# eCog001_Proto_PTH.net
KiCad netlist of a schematic drawn in EAGLE
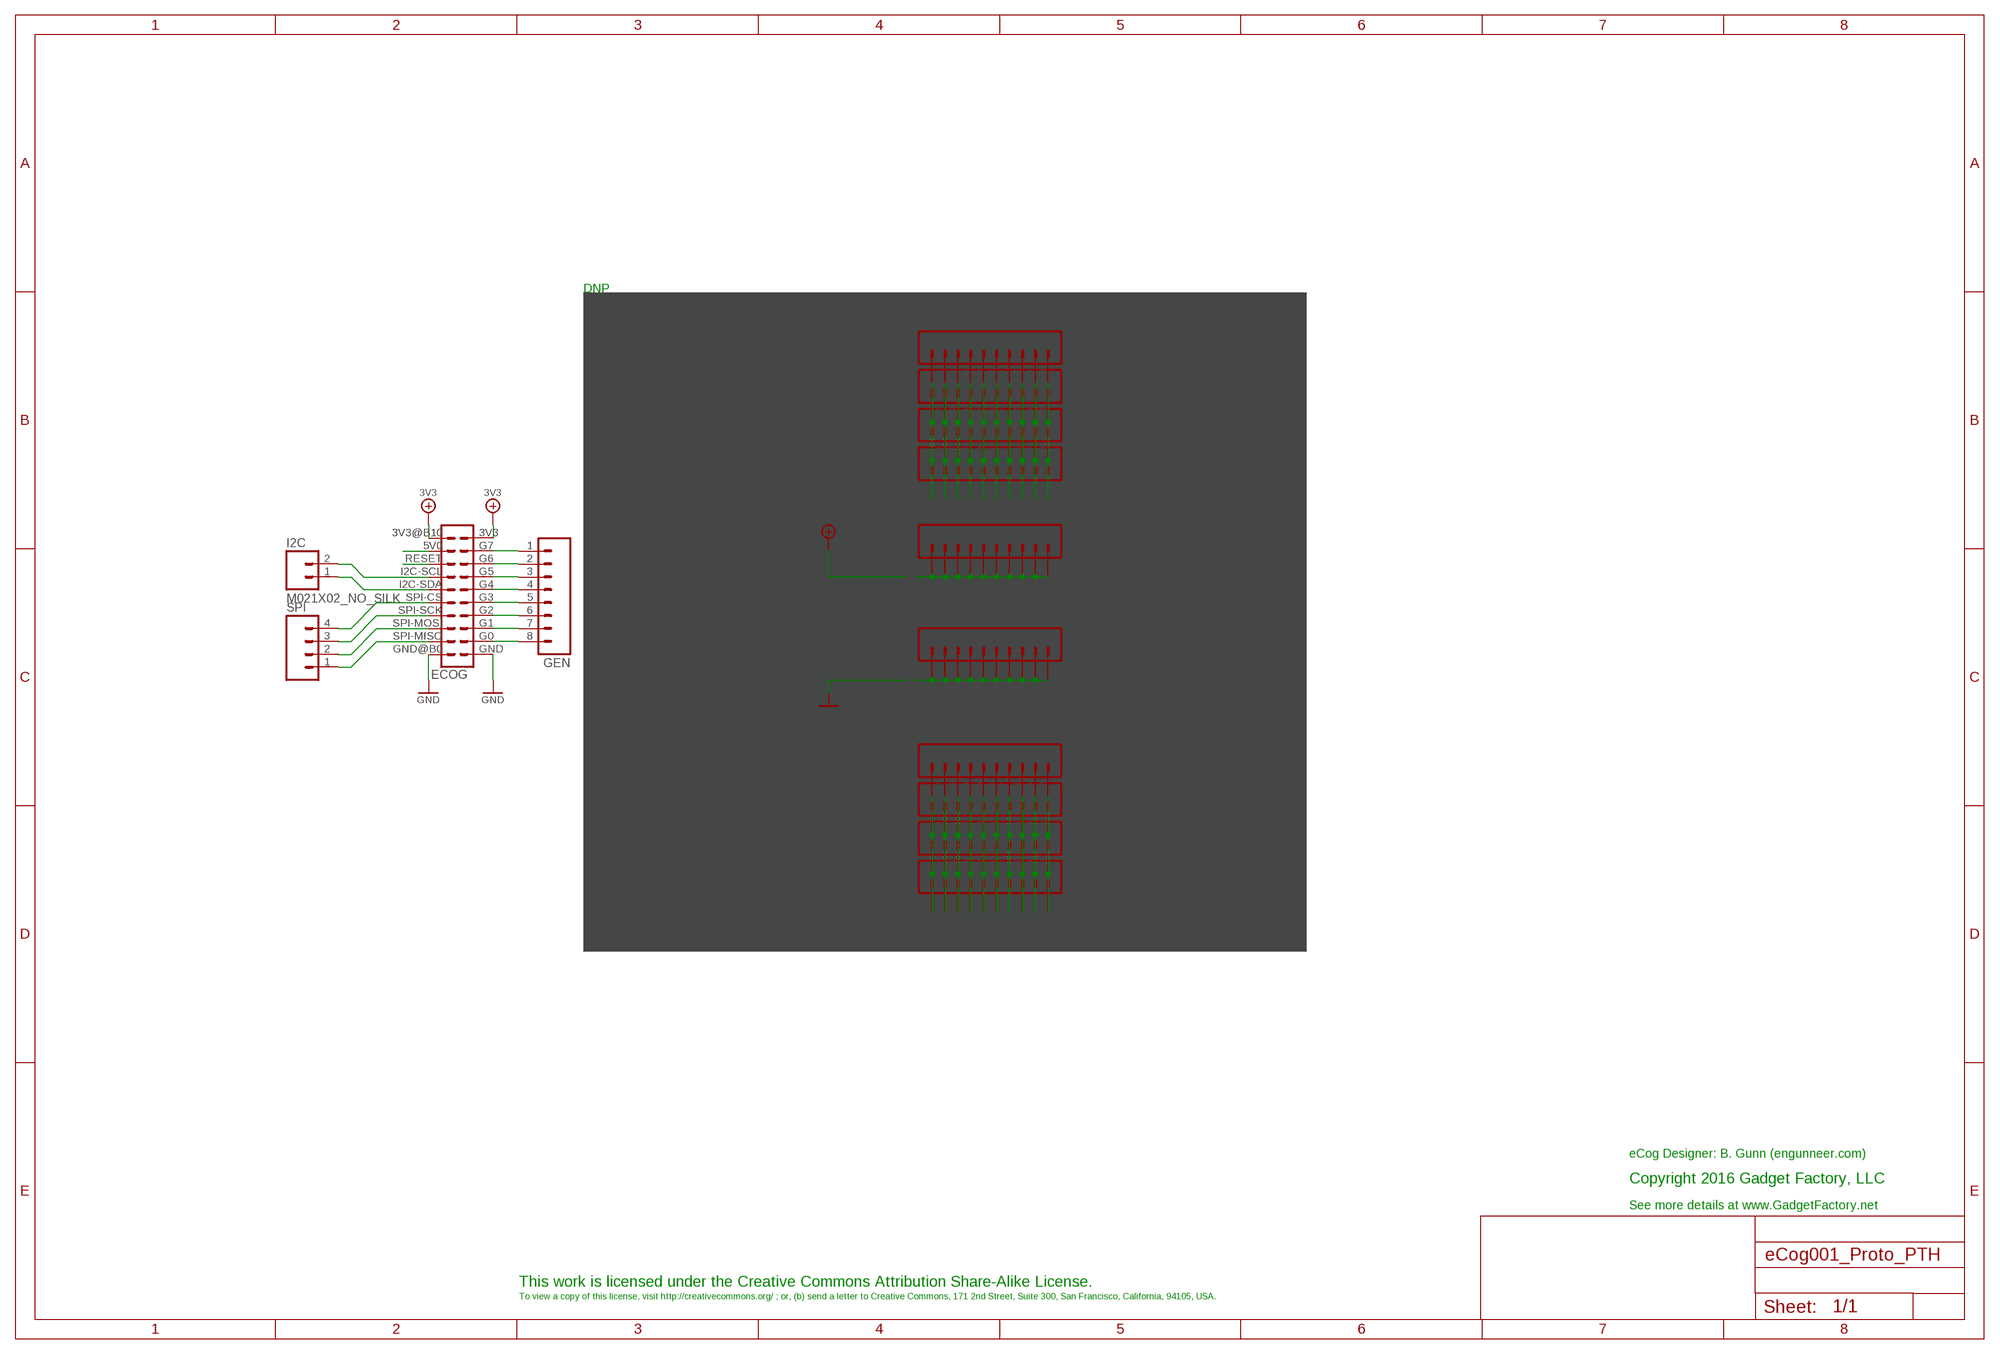
[diagram p0: schematic, sheet 1]

(export (version "E")
  (design (tool "Eeschema 10.0.6"))
  (components
    (comp (ref "ECOG")
      (value "ECOG_DUALTHROUGHHOLE")
      (footprint "eagle-import:ECOG_DUAL_TH")
      (libsource (lib "eagle-import") (part "ECOG_DUALTHROUGHHOLE"))
    )
    (comp (ref "GEN")
      (value "M08NO_SILK")
      (footprint "eagle-import:1X08_NO_SILK")
      (libsource (lib "eagle-import") (part "M08NO_SILK"))
    )
    (comp (ref "GND")
      (value "M10NO_SILK")
      (footprint "eagle-import:1X10_NO_SILK")
      (libsource (lib "eagle-import") (part "M10NO_SILK"))
    )
    (comp (ref "I2C")
      (value "M021X02_NO_SILK")
      (footprint "eagle-import:1X02_NO_SILK")
      (libsource (lib "eagle-import") (part "M021X02_NO_SILK"))
    )
    (comp (ref "P1")
      (value "M10NO_SILK")
      (footprint "eagle-import:1X10_NO_SILK")
      (libsource (lib "eagle-import") (part "M10NO_SILK"))
    )
    (comp (ref "P2")
      (value "M10NO_SILK")
      (footprint "eagle-import:1X10_NO_SILK")
      (libsource (lib "eagle-import") (part "M10NO_SILK"))
    )
    (comp (ref "P3")
      (value "M10NO_SILK")
      (footprint "eagle-import:1X10_NO_SILK")
      (libsource (lib "eagle-import") (part "M10NO_SILK"))
    )
    (comp (ref "P4")
      (value "M10NO_SILK")
      (footprint "eagle-import:1X10_NO_SILK")
      (libsource (lib "eagle-import") (part "M10NO_SILK"))
    )
    (comp (ref "P5")
      (value "M10NO_SILK")
      (footprint "eagle-import:1X10_NO_SILK")
      (libsource (lib "eagle-import") (part "M10NO_SILK"))
    )
    (comp (ref "P6")
      (value "M10NO_SILK")
      (footprint "eagle-import:1X10_NO_SILK")
      (libsource (lib "eagle-import") (part "M10NO_SILK"))
    )
    (comp (ref "P7")
      (value "M10NO_SILK")
      (footprint "eagle-import:1X10_NO_SILK")
      (libsource (lib "eagle-import") (part "M10NO_SILK"))
    )
    (comp (ref "P8")
      (value "M10NO_SILK")
      (footprint "eagle-import:1X10_NO_SILK")
      (libsource (lib "eagle-import") (part "M10NO_SILK"))
    )
    (comp (ref "SPI")
      (value "M041X04_NO_SILK")
      (footprint "eagle-import:1X04_NO_SILK")
      (libsource (lib "eagle-import") (part "M041X04_NO_SILK"))
    )
    (comp (ref "VCC")
      (value "M10NO_SILK")
      (footprint "eagle-import:1X10_NO_SILK")
      (libsource (lib "eagle-import") (part "M10NO_SILK"))
    )
  )
  (nets
    (net (code "1") (name "3V3") (class "Default")
      (node (ref "ECOG") (pin "3V3") (pinfunction "3V3_3V3") (pintype "passive"))
      (node (ref "ECOG") (pin "3V3@B10") (pinfunction "3V3_3V3@B10") (pintype "passive"))
      (node (ref "VCC") (pin "1") (pinfunction "1_1") (pintype "passive"))
      (node (ref "VCC") (pin "10") (pinfunction "10_10") (pintype "passive"))
      (node (ref "VCC") (pin "2") (pinfunction "2_2") (pintype "passive"))
      (node (ref "VCC") (pin "3") (pinfunction "3_3") (pintype "passive"))
      (node (ref "VCC") (pin "4") (pinfunction "4_4") (pintype "passive"))
      (node (ref "VCC") (pin "5") (pinfunction "5_5") (pintype "passive"))
      (node (ref "VCC") (pin "6") (pinfunction "6_6") (pintype "passive"))
      (node (ref "VCC") (pin "7") (pinfunction "7_7") (pintype "passive"))
      (node (ref "VCC") (pin "8") (pinfunction "8_8") (pintype "passive"))
      (node (ref "VCC") (pin "9") (pinfunction "9_9") (pintype "passive"))
    )
    (net (code "2") (name "GND") (class "Default")
      (node (ref "ECOG") (pin "GND") (pinfunction "GND_GND") (pintype "passive"))
      (node (ref "ECOG") (pin "GND@B0") (pinfunction "GND_GND@B0") (pintype "passive"))
      (node (ref "GND") (pin "1") (pinfunction "1_1") (pintype "passive"))
      (node (ref "GND") (pin "10") (pinfunction "10_10") (pintype "passive"))
      (node (ref "GND") (pin "2") (pinfunction "2_2") (pintype "passive"))
      (node (ref "GND") (pin "3") (pinfunction "3_3") (pintype "passive"))
      (node (ref "GND") (pin "4") (pinfunction "4_4") (pintype "passive"))
      (node (ref "GND") (pin "5") (pinfunction "5_5") (pintype "passive"))
      (node (ref "GND") (pin "6") (pinfunction "6_6") (pintype "passive"))
      (node (ref "GND") (pin "7") (pinfunction "7_7") (pintype "passive"))
      (node (ref "GND") (pin "8") (pinfunction "8_8") (pintype "passive"))
      (node (ref "GND") (pin "9") (pinfunction "9_9") (pintype "passive"))
    )
    (net (code "3") (name "Net-(ECOG-PadG0)") (class "Default")
      (node (ref "ECOG") (pin "G0") (pinfunction "G0_G0") (pintype "passive"))
      (node (ref "GEN") (pin "8") (pinfunction "8_8") (pintype "passive"))
    )
    (net (code "4") (name "Net-(ECOG-PadG1)") (class "Default")
      (node (ref "ECOG") (pin "G1") (pinfunction "G1_G1") (pintype "passive"))
      (node (ref "GEN") (pin "7") (pinfunction "7_7") (pintype "passive"))
    )
    (net (code "5") (name "Net-(ECOG-PadG2)") (class "Default")
      (node (ref "ECOG") (pin "G2") (pinfunction "G2_G2") (pintype "passive"))
      (node (ref "GEN") (pin "6") (pinfunction "6_6") (pintype "passive"))
    )
    (net (code "6") (name "Net-(ECOG-PadG3)") (class "Default")
      (node (ref "ECOG") (pin "G3") (pinfunction "G3_G3") (pintype "passive"))
      (node (ref "GEN") (pin "5") (pinfunction "5_5") (pintype "passive"))
    )
    (net (code "7") (name "Net-(ECOG-PadG4)") (class "Default")
      (node (ref "ECOG") (pin "G4") (pinfunction "G4_G4") (pintype "passive"))
      (node (ref "GEN") (pin "4") (pinfunction "4_4") (pintype "passive"))
    )
    (net (code "8") (name "Net-(ECOG-PadG5)") (class "Default")
      (node (ref "ECOG") (pin "G5") (pinfunction "G5_G5") (pintype "passive"))
      (node (ref "GEN") (pin "3") (pinfunction "3_3") (pintype "passive"))
    )
    (net (code "9") (name "Net-(ECOG-PadG6)") (class "Default")
      (node (ref "ECOG") (pin "G6") (pinfunction "G6_G6") (pintype "passive"))
      (node (ref "GEN") (pin "2") (pinfunction "2_2") (pintype "passive"))
    )
    (net (code "10") (name "Net-(ECOG-PadG7)") (class "Default")
      (node (ref "ECOG") (pin "G7") (pinfunction "G7_G7") (pintype "passive"))
      (node (ref "GEN") (pin "1") (pinfunction "1_1") (pintype "passive"))
    )
    (net (code "11") (name "Net-(ECOG-PadI2C-SCL)") (class "Default")
      (node (ref "ECOG") (pin "I2C-SCL") (pinfunction "I2C-SCL_I2C-SCL") (pintype "passive"))
      (node (ref "I2C") (pin "2") (pinfunction "2_2") (pintype "passive"))
    )
    (net (code "12") (name "Net-(ECOG-PadI2C-SDA)") (class "Default")
      (node (ref "ECOG") (pin "I2C-SDA") (pinfunction "I2C-SDA_I2C-SDA") (pintype "passive"))
      (node (ref "I2C") (pin "1") (pinfunction "1_1") (pintype "passive"))
    )
    (net (code "13") (name "Net-(ECOG-PadSPI-CS)") (class "Default")
      (node (ref "ECOG") (pin "SPI-CS") (pinfunction "SPI-CS_SPI-CS") (pintype "passive"))
      (node (ref "SPI") (pin "4") (pinfunction "4_4") (pintype "passive"))
    )
    (net (code "14") (name "Net-(ECOG-PadSPI-MISO)") (class "Default")
      (node (ref "ECOG") (pin "SPI-MISO") (pinfunction "SPI-MISO_SPI-MISO") (pintype "passive"))
      (node (ref "SPI") (pin "1") (pinfunction "1_1") (pintype "passive"))
    )
    (net (code "15") (name "Net-(ECOG-PadSPI-MOSI)") (class "Default")
      (node (ref "ECOG") (pin "SPI-MOSI") (pinfunction "SPI-MOSI_SPI-MOSI") (pintype "passive"))
      (node (ref "SPI") (pin "2") (pinfunction "2_2") (pintype "passive"))
    )
    (net (code "16") (name "Net-(ECOG-PadSPI-SCK)") (class "Default")
      (node (ref "ECOG") (pin "SPI-SCK") (pinfunction "SPI-SCK_SPI-SCK") (pintype "passive"))
      (node (ref "SPI") (pin "3") (pinfunction "3_3") (pintype "passive"))
    )
    (net (code "17") (name "Net-(P1-Pad1)") (class "Default")
      (node (ref "P1") (pin "1") (pinfunction "1_1") (pintype "passive"))
      (node (ref "P2") (pin "1") (pinfunction "1_1") (pintype "passive"))
      (node (ref "P3") (pin "1") (pinfunction "1_1") (pintype "passive"))
      (node (ref "P4") (pin "1") (pinfunction "1_1") (pintype "passive"))
    )
    (net (code "18") (name "Net-(P1-Pad2)") (class "Default")
      (node (ref "P1") (pin "2") (pinfunction "2_2") (pintype "passive"))
      (node (ref "P2") (pin "2") (pinfunction "2_2") (pintype "passive"))
      (node (ref "P3") (pin "2") (pinfunction "2_2") (pintype "passive"))
      (node (ref "P4") (pin "2") (pinfunction "2_2") (pintype "passive"))
    )
    (net (code "19") (name "Net-(P1-Pad3)") (class "Default")
      (node (ref "P1") (pin "3") (pinfunction "3_3") (pintype "passive"))
      (node (ref "P2") (pin "3") (pinfunction "3_3") (pintype "passive"))
      (node (ref "P3") (pin "3") (pinfunction "3_3") (pintype "passive"))
      (node (ref "P4") (pin "3") (pinfunction "3_3") (pintype "passive"))
    )
    (net (code "20") (name "Net-(P1-Pad4)") (class "Default")
      (node (ref "P1") (pin "4") (pinfunction "4_4") (pintype "passive"))
      (node (ref "P2") (pin "4") (pinfunction "4_4") (pintype "passive"))
      (node (ref "P3") (pin "4") (pinfunction "4_4") (pintype "passive"))
      (node (ref "P4") (pin "4") (pinfunction "4_4") (pintype "passive"))
    )
    (net (code "21") (name "Net-(P1-Pad5)") (class "Default")
      (node (ref "P1") (pin "5") (pinfunction "5_5") (pintype "passive"))
      (node (ref "P2") (pin "5") (pinfunction "5_5") (pintype "passive"))
      (node (ref "P3") (pin "5") (pinfunction "5_5") (pintype "passive"))
      (node (ref "P4") (pin "5") (pinfunction "5_5") (pintype "passive"))
    )
    (net (code "22") (name "Net-(P1-Pad6)") (class "Default")
      (node (ref "P1") (pin "6") (pinfunction "6_6") (pintype "passive"))
      (node (ref "P2") (pin "6") (pinfunction "6_6") (pintype "passive"))
      (node (ref "P3") (pin "6") (pinfunction "6_6") (pintype "passive"))
      (node (ref "P4") (pin "6") (pinfunction "6_6") (pintype "passive"))
    )
    (net (code "23") (name "Net-(P1-Pad7)") (class "Default")
      (node (ref "P1") (pin "7") (pinfunction "7_7") (pintype "passive"))
      (node (ref "P2") (pin "7") (pinfunction "7_7") (pintype "passive"))
      (node (ref "P3") (pin "7") (pinfunction "7_7") (pintype "passive"))
      (node (ref "P4") (pin "7") (pinfunction "7_7") (pintype "passive"))
    )
    (net (code "24") (name "Net-(P1-Pad8)") (class "Default")
      (node (ref "P1") (pin "8") (pinfunction "8_8") (pintype "passive"))
      (node (ref "P2") (pin "8") (pinfunction "8_8") (pintype "passive"))
      (node (ref "P3") (pin "8") (pinfunction "8_8") (pintype "passive"))
      (node (ref "P4") (pin "8") (pinfunction "8_8") (pintype "passive"))
    )
    (net (code "25") (name "Net-(P1-Pad9)") (class "Default")
      (node (ref "P1") (pin "9") (pinfunction "9_9") (pintype "passive"))
      (node (ref "P2") (pin "9") (pinfunction "9_9") (pintype "passive"))
      (node (ref "P3") (pin "9") (pinfunction "9_9") (pintype "passive"))
      (node (ref "P4") (pin "9") (pinfunction "9_9") (pintype "passive"))
    )
    (net (code "26") (name "Net-(P1-Pad10)") (class "Default")
      (node (ref "P1") (pin "10") (pinfunction "10_10") (pintype "passive"))
      (node (ref "P2") (pin "10") (pinfunction "10_10") (pintype "passive"))
      (node (ref "P3") (pin "10") (pinfunction "10_10") (pintype "passive"))
      (node (ref "P4") (pin "10") (pinfunction "10_10") (pintype "passive"))
    )
    (net (code "27") (name "Net-(P5-Pad1)") (class "Default")
      (node (ref "P5") (pin "1") (pinfunction "1_1") (pintype "passive"))
      (node (ref "P6") (pin "1") (pinfunction "1_1") (pintype "passive"))
      (node (ref "P7") (pin "1") (pinfunction "1_1") (pintype "passive"))
      (node (ref "P8") (pin "1") (pinfunction "1_1") (pintype "passive"))
    )
    (net (code "28") (name "Net-(P5-Pad2)") (class "Default")
      (node (ref "P5") (pin "2") (pinfunction "2_2") (pintype "passive"))
      (node (ref "P6") (pin "2") (pinfunction "2_2") (pintype "passive"))
      (node (ref "P7") (pin "2") (pinfunction "2_2") (pintype "passive"))
      (node (ref "P8") (pin "2") (pinfunction "2_2") (pintype "passive"))
    )
    (net (code "29") (name "Net-(P5-Pad3)") (class "Default")
      (node (ref "P5") (pin "3") (pinfunction "3_3") (pintype "passive"))
      (node (ref "P6") (pin "3") (pinfunction "3_3") (pintype "passive"))
      (node (ref "P7") (pin "3") (pinfunction "3_3") (pintype "passive"))
      (node (ref "P8") (pin "3") (pinfunction "3_3") (pintype "passive"))
    )
    (net (code "30") (name "Net-(P5-Pad4)") (class "Default")
      (node (ref "P5") (pin "4") (pinfunction "4_4") (pintype "passive"))
      (node (ref "P6") (pin "4") (pinfunction "4_4") (pintype "passive"))
      (node (ref "P7") (pin "4") (pinfunction "4_4") (pintype "passive"))
      (node (ref "P8") (pin "4") (pinfunction "4_4") (pintype "passive"))
    )
    (net (code "31") (name "Net-(P5-Pad5)") (class "Default")
      (node (ref "P5") (pin "5") (pinfunction "5_5") (pintype "passive"))
      (node (ref "P6") (pin "5") (pinfunction "5_5") (pintype "passive"))
      (node (ref "P7") (pin "5") (pinfunction "5_5") (pintype "passive"))
      (node (ref "P8") (pin "5") (pinfunction "5_5") (pintype "passive"))
    )
    (net (code "32") (name "Net-(P5-Pad6)") (class "Default")
      (node (ref "P5") (pin "6") (pinfunction "6_6") (pintype "passive"))
      (node (ref "P6") (pin "6") (pinfunction "6_6") (pintype "passive"))
      (node (ref "P7") (pin "6") (pinfunction "6_6") (pintype "passive"))
      (node (ref "P8") (pin "6") (pinfunction "6_6") (pintype "passive"))
    )
    (net (code "33") (name "Net-(P5-Pad7)") (class "Default")
      (node (ref "P5") (pin "7") (pinfunction "7_7") (pintype "passive"))
      (node (ref "P6") (pin "7") (pinfunction "7_7") (pintype "passive"))
      (node (ref "P7") (pin "7") (pinfunction "7_7") (pintype "passive"))
      (node (ref "P8") (pin "7") (pinfunction "7_7") (pintype "passive"))
    )
    (net (code "34") (name "Net-(P5-Pad8)") (class "Default")
      (node (ref "P5") (pin "8") (pinfunction "8_8") (pintype "passive"))
      (node (ref "P6") (pin "8") (pinfunction "8_8") (pintype "passive"))
      (node (ref "P7") (pin "8") (pinfunction "8_8") (pintype "passive"))
      (node (ref "P8") (pin "8") (pinfunction "8_8") (pintype "passive"))
    )
    (net (code "35") (name "Net-(P5-Pad9)") (class "Default")
      (node (ref "P5") (pin "9") (pinfunction "9_9") (pintype "passive"))
      (node (ref "P6") (pin "9") (pinfunction "9_9") (pintype "passive"))
      (node (ref "P7") (pin "9") (pinfunction "9_9") (pintype "passive"))
      (node (ref "P8") (pin "9") (pinfunction "9_9") (pintype "passive"))
    )
    (net (code "36") (name "Net-(P5-Pad10)") (class "Default")
      (node (ref "P5") (pin "10") (pinfunction "10_10") (pintype "passive"))
      (node (ref "P6") (pin "10") (pinfunction "10_10") (pintype "passive"))
      (node (ref "P7") (pin "10") (pinfunction "10_10") (pintype "passive"))
      (node (ref "P8") (pin "10") (pinfunction "10_10") (pintype "passive"))
    )
    (net (code "37") (name "unconnected-(ECOG-5V-Pad5V0)") (class "Default")
      (node (ref "ECOG") (pin "5V0") (pinfunction "5V_5V0") (pintype "passive"))
    )
    (net (code "38") (name "unconnected-(ECOG-PadRESET)") (class "Default")
      (node (ref "ECOG") (pin "RESET") (pinfunction "RESET_RESET") (pintype "passive"))
    )
  )
)
